# PeterParker.net
KiCad netlist of a schematic drawn in Altium Designer
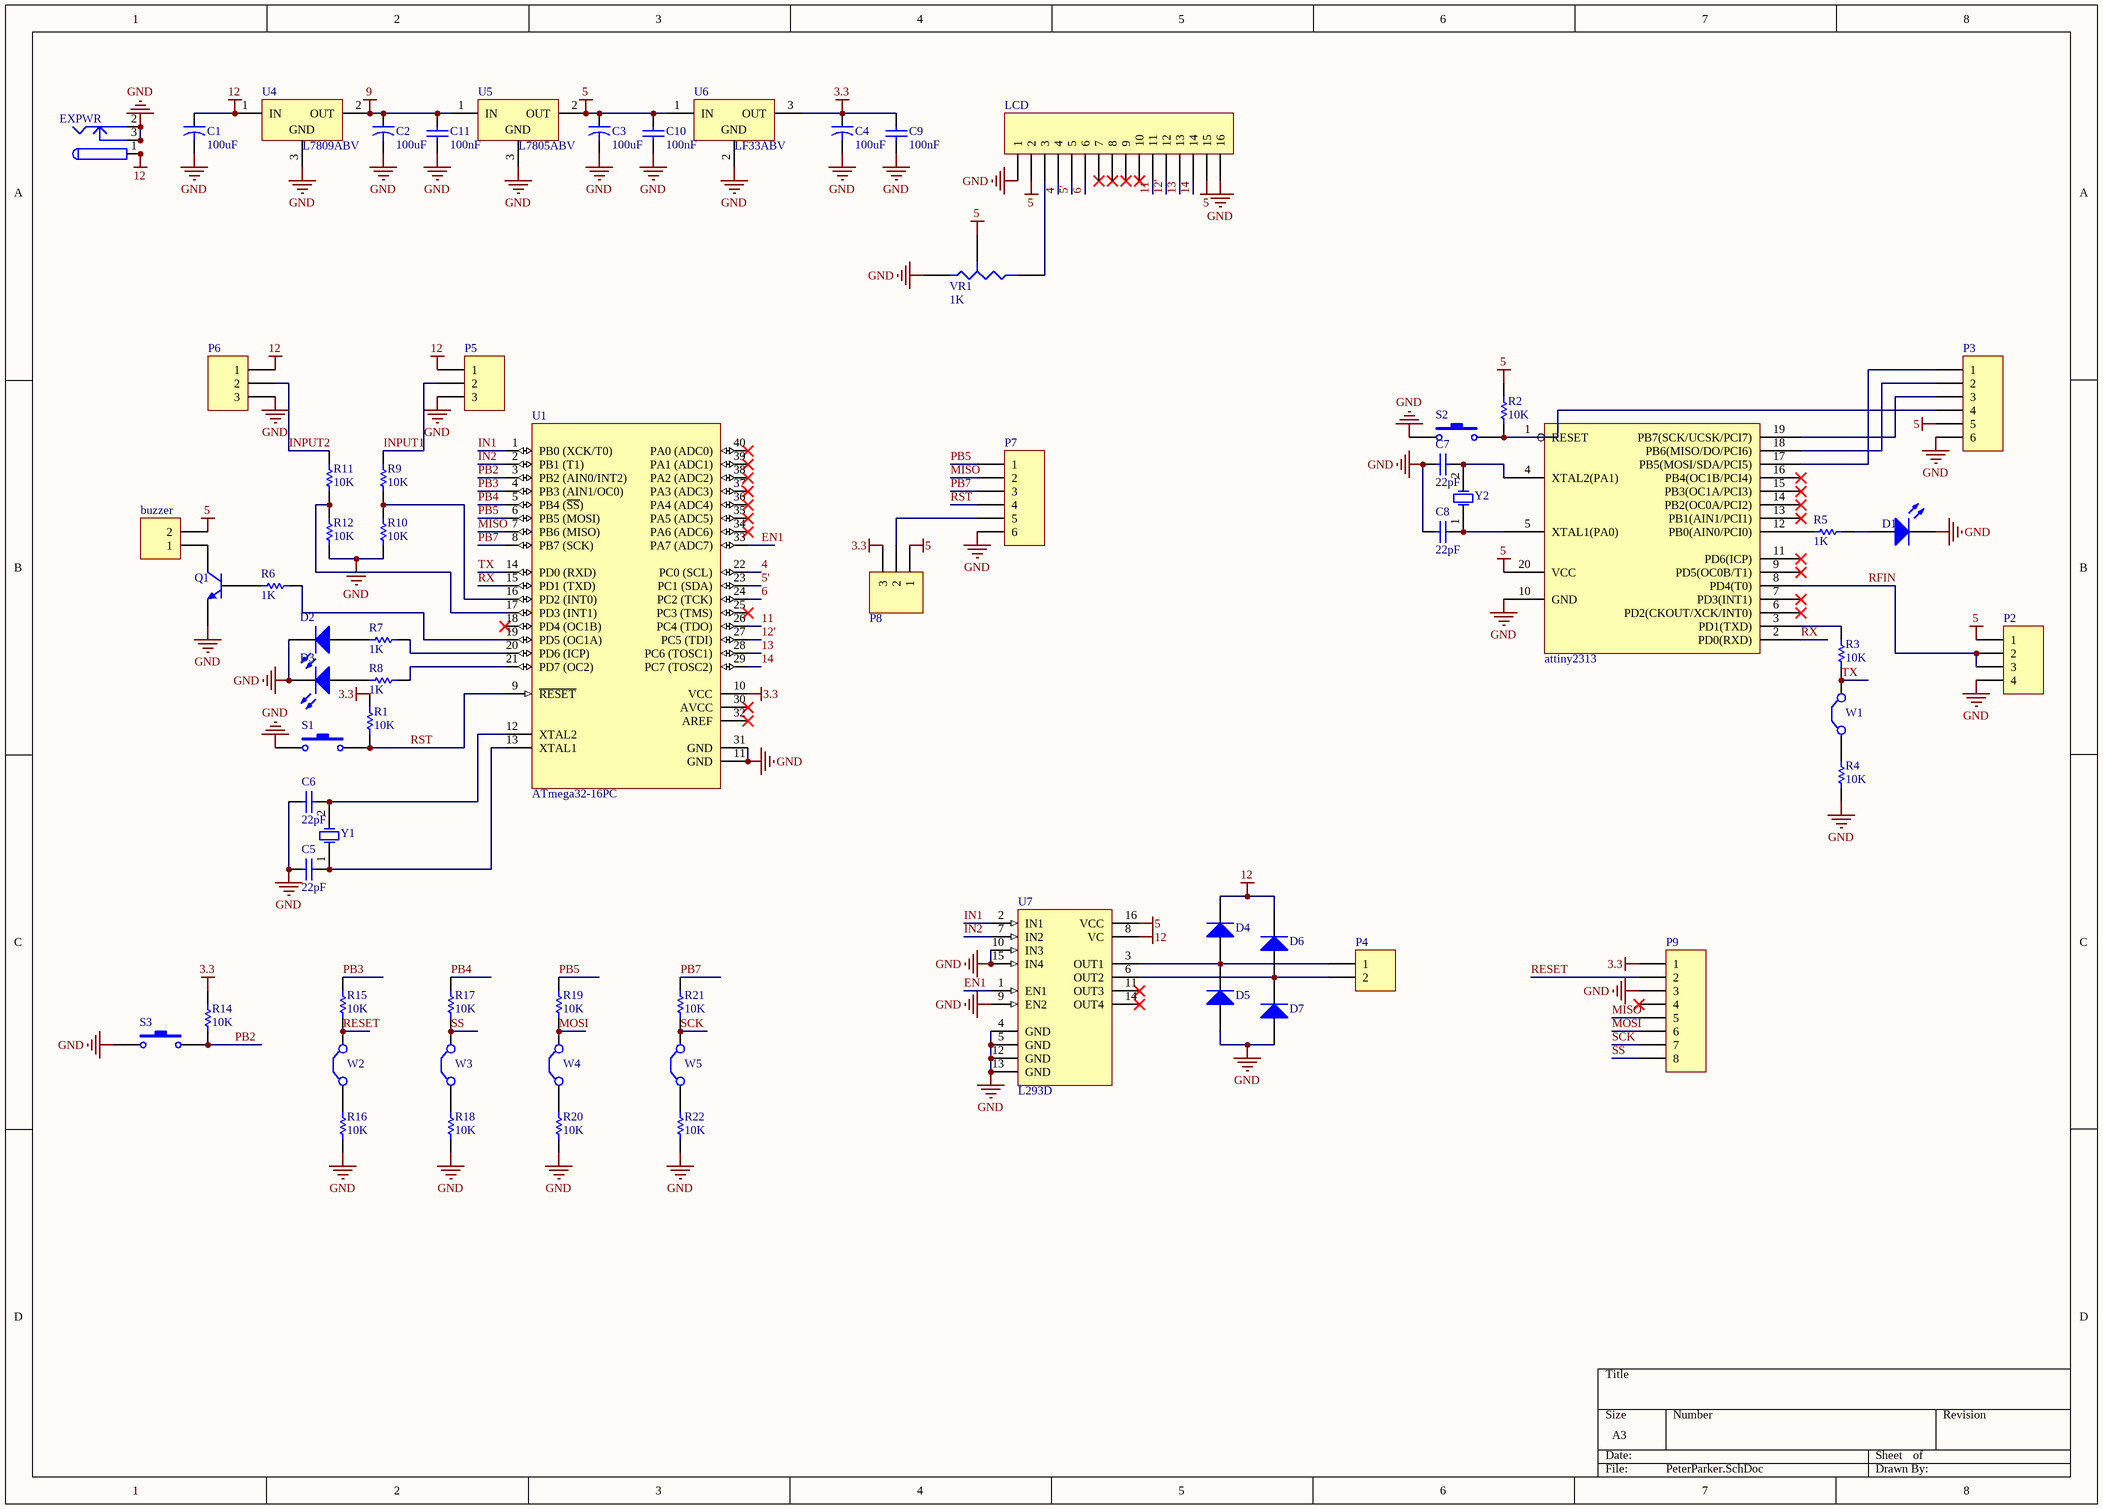
[diagram p0: PeterParker.SchDoc]

(export (version "E")
  (design (tool "Eeschema 10.0.6"))
  (components
    (comp (ref "attiny2313")
      (value "attiny2313")
      (footprint "DIP20")
      (libsource (lib "attiny2313") (part "attiny2313"))
    )
    (comp (ref "buzzer")
      (value "Header 2")
      (footprint "buzzer")
      (description "Header, 2-Pin")
      (fields (field (name "PUBLISHER") "Altium Limited"))
      (libsource (lib "Miscellaneous Connectors") (part "Header 2"))
    )
    (comp (ref "C1")
      (value "100uF")
      (footprint "CAPR5-4X5")
      (description "Capacitor")
      (fields (field (name "Comment") "Cap2") (field (name "PUBLISHER") "Altium Limited"))
      (libsource (lib "Miscellaneous Devices") (part "Cap2"))
    )
    (comp (ref "C2")
      (value "100uF")
      (footprint "CAPR5-4X5")
      (description "Capacitor")
      (fields (field (name "Comment") "Cap2") (field (name "PUBLISHER") "Altium Limited"))
      (libsource (lib "Miscellaneous Devices") (part "Cap2"))
    )
    (comp (ref "C3")
      (value "100uF")
      (footprint "CAPR5-4X5")
      (description "Capacitor")
      (fields (field (name "Comment") "Cap2") (field (name "PUBLISHER") "Altium Limited"))
      (libsource (lib "Miscellaneous Devices") (part "Cap2"))
    )
    (comp (ref "C4")
      (value "100uF")
      (footprint "CAPR5-4X5")
      (description "Capacitor")
      (fields (field (name "Comment") "Cap2") (field (name "PUBLISHER") "Altium Limited"))
      (libsource (lib "Miscellaneous Devices") (part "Cap2"))
    )
    (comp (ref "C5")
      (value "22pF")
      (footprint "tinycap")
      (description "Capacitor")
      (fields (field (name "Comment") "Cap") (field (name "PUBLISHER") "Altium Limited"))
      (libsource (lib "Miscellaneous Devices") (part "Cap"))
    )
    (comp (ref "C6")
      (value "22pF")
      (footprint "tinycap")
      (description "Capacitor")
      (fields (field (name "Comment") "Cap") (field (name "PUBLISHER") "Altium Limited"))
      (libsource (lib "Miscellaneous Devices") (part "Cap"))
    )
    (comp (ref "C7")
      (value "22pF")
      (footprint "tinycap")
      (description "Capacitor")
      (fields (field (name "Comment") "Cap") (field (name "PUBLISHER") "Altium Limited"))
      (libsource (lib "Miscellaneous Devices") (part "Cap"))
    )
    (comp (ref "C8")
      (value "22pF")
      (footprint "tinycap")
      (description "Capacitor")
      (fields (field (name "Comment") "Cap") (field (name "PUBLISHER") "Altium Limited"))
      (libsource (lib "Miscellaneous Devices") (part "Cap"))
    )
    (comp (ref "C9")
      (value "100nF")
      (footprint "RAD-0.2")
      (description "Capacitor")
      (fields (field (name "Comment") "Cap") (field (name "PUBLISHER") "Altium Limited"))
      (libsource (lib "Miscellaneous Devices") (part "Cap"))
    )
    (comp (ref "C10")
      (value "100nF")
      (footprint "RAD-0.2")
      (description "Capacitor")
      (fields (field (name "Comment") "Cap") (field (name "PUBLISHER") "Altium Limited"))
      (libsource (lib "Miscellaneous Devices") (part "Cap"))
    )
    (comp (ref "C11")
      (value "100nF")
      (footprint "RAD-0.2")
      (description "Capacitor")
      (fields (field (name "Comment") "Cap") (field (name "PUBLISHER") "Altium Limited"))
      (libsource (lib "Miscellaneous Devices") (part "Cap"))
    )
    (comp (ref "D1")
      (value "LED0")
      (footprint "LED3MM")
      (description "Typical INFRARED GaAs LED")
      (fields (field (name "PUBLISHER") "Altium Limited"))
      (libsource (lib "Miscellaneous Devices") (part "LED0"))
    )
    (comp (ref "D2")
      (value "LED0")
      (footprint "LED3MM")
      (description "Typical INFRARED GaAs LED")
      (fields (field (name "PUBLISHER") "Altium Limited"))
      (libsource (lib "Miscellaneous Devices") (part "LED0"))
    )
    (comp (ref "D3")
      (value "LED0")
      (footprint "LED3MM")
      (description "Typical INFRARED GaAs LED")
      (fields (field (name "PUBLISHER") "Altium Limited"))
      (libsource (lib "Miscellaneous Devices") (part "LED0"))
    )
    (comp (ref "D4")
      (value "Diode 1N4148")
      (footprint "Miscellaneous Devices:AXIAL-0.3")
      (description "High Conductance Fast Diode")
      (fields (field (name "PUBLISHER") "Altium Limited"))
      (libsource (lib "Miscellaneous Devices") (part "Diode 1N4148"))
    )
    (comp (ref "D5")
      (value "Diode 1N4148")
      (footprint "Miscellaneous Devices:AXIAL-0.3")
      (description "High Conductance Fast Diode")
      (fields (field (name "PUBLISHER") "Altium Limited"))
      (libsource (lib "Miscellaneous Devices") (part "Diode 1N4148"))
    )
    (comp (ref "D6")
      (value "Diode 1N4148")
      (footprint "Miscellaneous Devices:AXIAL-0.3")
      (description "High Conductance Fast Diode")
      (fields (field (name "PUBLISHER") "Altium Limited"))
      (libsource (lib "Miscellaneous Devices") (part "Diode 1N4148"))
    )
    (comp (ref "D7")
      (value "Diode 1N4148")
      (footprint "Miscellaneous Devices:AXIAL-0.3")
      (description "High Conductance Fast Diode")
      (fields (field (name "PUBLISHER") "Altium Limited"))
      (libsource (lib "Miscellaneous Devices") (part "Diode 1N4148"))
    )
    (comp (ref "EXPWR")
      (value "PWR2.5")
      (footprint "JACK1")
      (description "Low Voltage Power Supply Connector")
      (fields (field (name "PUBLISHER") "Altium Limited"))
      (libsource (lib "Miscellaneous Connectors") (part "PWR2.5"))
    )
    (comp (ref "LCD")
      (value "Header 16")
      (footprint "H1X16F")
      (description "Header, 16-Pin")
      (fields (field (name "PUBLISHER") "Altium Limited"))
      (libsource (lib "Miscellaneous Connectors") (part "Header 16"))
    )
    (comp (ref "P2")
      (value "Header 4")
      (footprint "H1X04F")
      (description "Header, 4-Pin")
      (fields (field (name "PUBLISHER") "Altium Limited"))
      (libsource (lib "Miscellaneous Connectors") (part "Header 4"))
    )
    (comp (ref "P3")
      (value "Header 6")
      (footprint "H1X06F")
      (description "Header, 6-Pin")
      (fields (field (name "PUBLISHER") "Altium Limited"))
      (libsource (lib "Miscellaneous Connectors") (part "Header 6"))
    )
    (comp (ref "P4")
      (value "Header 2")
      (footprint "H1X02F")
      (description "Header, 2-Pin")
      (fields (field (name "PUBLISHER") "Altium Limited"))
      (libsource (lib "") (part "Header 2_1"))
    )
    (comp (ref "P5")
      (value "Header 3")
      (footprint "H1X03F")
      (description "Header, 3-Pin")
      (fields (field (name "PUBLISHER") "Altium Limited"))
      (libsource (lib "") (part "Header 3_1"))
    )
    (comp (ref "P6")
      (value "Header 3")
      (footprint "H1X03F")
      (description "Header, 3-Pin")
      (fields (field (name "PUBLISHER") "Altium Limited"))
      (libsource (lib "Miscellaneous Connectors") (part "Header 3"))
    )
    (comp (ref "P7")
      (value "Header 6")
      (footprint "H1X06F")
      (description "Header, 6-Pin")
      (fields (field (name "PUBLISHER") "Altium Limited"))
      (libsource (lib "Miscellaneous Connectors") (part "Header 6"))
    )
    (comp (ref "P8")
      (value "Header 3")
      (footprint "H1X03F")
      (description "Header, 3-Pin")
      (fields (field (name "PUBLISHER") "Altium Limited"))
      (libsource (lib "Miscellaneous Connectors") (part "Header 3"))
    )
    (comp (ref "P9")
      (value "Header 8")
      (footprint "H1X08F")
      (description "Header, 8-Pin")
      (fields (field (name "PUBLISHER") "Altium Limited"))
      (libsource (lib "Miscellaneous Connectors") (part "Header 8"))
    )
    (comp (ref "Q1")
      (value "BC547")
      (footprint "SOT54")
      (description "NPN General-purpose Transistor")
      (fields (field (name "PUBLISHER") "Altium Limited"))
      (libsource (lib "Philips Discrete BJT - Low Power") (part "BC547"))
    )
    (comp (ref "R1")
      (value "10K")
      (footprint "AXIAL-0.3")
      (description "Resistor")
      (fields (field (name "Comment") "Res1") (field (name "PUBLISHER") "Altium Limited"))
      (libsource (lib "Miscellaneous Devices") (part "Res1"))
    )
    (comp (ref "R2")
      (value "10K")
      (footprint "AXIAL-0.3")
      (description "Resistor")
      (fields (field (name "Comment") "Res1") (field (name "PUBLISHER") "Altium Limited"))
      (libsource (lib "Miscellaneous Devices") (part "Res1"))
    )
    (comp (ref "R3")
      (value "10K")
      (footprint "AXIAL-0.3")
      (description "Resistor")
      (fields (field (name "Comment") "Res1") (field (name "PUBLISHER") "Altium Limited"))
      (libsource (lib "Miscellaneous Devices") (part "Res1"))
    )
    (comp (ref "R4")
      (value "10K")
      (footprint "AXIAL-0.3")
      (description "Resistor")
      (fields (field (name "Comment") "Res1") (field (name "PUBLISHER") "Altium Limited"))
      (libsource (lib "Miscellaneous Devices") (part "Res1"))
    )
    (comp (ref "R5")
      (value "1K")
      (footprint "AXIAL-0.3")
      (description "Resistor")
      (fields (field (name "Comment") "Res1") (field (name "PUBLISHER") "Altium Limited"))
      (libsource (lib "Miscellaneous Devices") (part "Res1"))
    )
    (comp (ref "R6")
      (value "1K")
      (footprint "AXIAL-0.3")
      (description "Resistor")
      (fields (field (name "Comment") "Res1") (field (name "PUBLISHER") "Altium Limited"))
      (libsource (lib "Miscellaneous Devices") (part "Res1"))
    )
    (comp (ref "R7")
      (value "1K")
      (footprint "AXIAL-0.3")
      (description "Resistor")
      (fields (field (name "Comment") "Res1") (field (name "PUBLISHER") "Altium Limited"))
      (libsource (lib "Miscellaneous Devices") (part "Res1"))
    )
    (comp (ref "R8")
      (value "1K")
      (footprint "AXIAL-0.3")
      (description "Resistor")
      (fields (field (name "Comment") "Res1") (field (name "PUBLISHER") "Altium Limited"))
      (libsource (lib "Miscellaneous Devices") (part "Res1"))
    )
    (comp (ref "R9")
      (value "10K")
      (footprint "AXIAL-0.3")
      (description "Resistor")
      (fields (field (name "Comment") "Res1") (field (name "PUBLISHER") "Altium Limited"))
      (libsource (lib "Miscellaneous Devices") (part "Res1"))
    )
    (comp (ref "R10")
      (value "10K")
      (footprint "AXIAL-0.3")
      (description "Resistor")
      (fields (field (name "Comment") "Res1") (field (name "PUBLISHER") "Altium Limited"))
      (libsource (lib "Miscellaneous Devices") (part "Res1"))
    )
    (comp (ref "R11")
      (value "10K")
      (footprint "AXIAL-0.3")
      (description "Resistor")
      (fields (field (name "Comment") "Res1") (field (name "PUBLISHER") "Altium Limited"))
      (libsource (lib "Miscellaneous Devices") (part "Res1"))
    )
    (comp (ref "R12")
      (value "10K")
      (footprint "AXIAL-0.3")
      (description "Resistor")
      (fields (field (name "Comment") "Res1") (field (name "PUBLISHER") "Altium Limited"))
      (libsource (lib "Miscellaneous Devices") (part "Res1"))
    )
    (comp (ref "R14")
      (value "10K")
      (footprint "AXIAL-0.3")
      (description "Resistor")
      (fields (field (name "Comment") "Res1") (field (name "PUBLISHER") "Altium Limited"))
      (libsource (lib "Miscellaneous Devices") (part "Res1"))
    )
    (comp (ref "R15")
      (value "10K")
      (footprint "AXIAL-0.3")
      (description "Resistor")
      (fields (field (name "Comment") "Res1") (field (name "PUBLISHER") "Altium Limited"))
      (libsource (lib "Miscellaneous Devices") (part "Res1"))
    )
    (comp (ref "R16")
      (value "10K")
      (footprint "AXIAL-0.3")
      (description "Resistor")
      (fields (field (name "Comment") "Res1") (field (name "PUBLISHER") "Altium Limited"))
      (libsource (lib "Miscellaneous Devices") (part "Res1"))
    )
    (comp (ref "R17")
      (value "10K")
      (footprint "AXIAL-0.3")
      (description "Resistor")
      (fields (field (name "Comment") "Res1") (field (name "PUBLISHER") "Altium Limited"))
      (libsource (lib "Miscellaneous Devices") (part "Res1"))
    )
    (comp (ref "R18")
      (value "10K")
      (footprint "AXIAL-0.3")
      (description "Resistor")
      (fields (field (name "Comment") "Res1") (field (name "PUBLISHER") "Altium Limited"))
      (libsource (lib "Miscellaneous Devices") (part "Res1"))
    )
    (comp (ref "R19")
      (value "10K")
      (footprint "AXIAL-0.3")
      (description "Resistor")
      (fields (field (name "Comment") "Res1") (field (name "PUBLISHER") "Altium Limited"))
      (libsource (lib "Miscellaneous Devices") (part "Res1"))
    )
    (comp (ref "R20")
      (value "10K")
      (footprint "AXIAL-0.3")
      (description "Resistor")
      (fields (field (name "Comment") "Res1") (field (name "PUBLISHER") "Altium Limited"))
      (libsource (lib "Miscellaneous Devices") (part "Res1"))
    )
    (comp (ref "R21")
      (value "10K")
      (footprint "AXIAL-0.3")
      (description "Resistor")
      (fields (field (name "Comment") "Res1") (field (name "PUBLISHER") "Altium Limited"))
      (libsource (lib "Miscellaneous Devices") (part "Res1"))
    )
    (comp (ref "R22")
      (value "10K")
      (footprint "AXIAL-0.3")
      (description "Resistor")
      (fields (field (name "Comment") "Res1") (field (name "PUBLISHER") "Altium Limited"))
      (libsource (lib "Miscellaneous Devices") (part "Res1"))
    )
    (comp (ref "S1")
      (value "SW-PB")
      (footprint "PB4")
      (description "Switch")
      (fields (field (name "PUBLISHER") "Altium Limited"))
      (libsource (lib "Miscellaneous Devices") (part "SW-PB"))
    )
    (comp (ref "S2")
      (value "SW-PB")
      (footprint "PB4")
      (description "Switch")
      (fields (field (name "PUBLISHER") "Altium Limited"))
      (libsource (lib "Miscellaneous Devices") (part "SW-PB"))
    )
    (comp (ref "S3")
      (value "SW-PB")
      (footprint "PB4")
      (description "Switch")
      (fields (field (name "PUBLISHER") "Altium Limited"))
      (libsource (lib "Miscellaneous Devices") (part "SW-PB"))
    )
    (comp (ref "U1")
      (value "ATmega32-16PC")
      (footprint "40P6")
      (description "8-Bit AVR Microcontroller with 32K Bytes of In-System Programmable Flash Memory")
      (fields (field (name "PUBLISHER") "Altium Limited"))
      (libsource (lib "Atmel Microcontroller 8-Bit AVR") (part "ATmega32-16PC"))
    )
    (comp (ref "U4")
      (value "L7809ABV")
      (footprint "TO220ABN")
      (description "Precision 1A Regulator")
      (fields (field (name "PUBLISHER") "Altium Limited"))
      (libsource (lib "ST Power Mgt Voltage Regulator") (part "L7809ABV"))
    )
    (comp (ref "U5")
      (value "L7805ABV")
      (footprint "TO220ABN")
      (description "Precision 1A Regulator")
      (fields (field (name "PUBLISHER") "Altium Limited"))
      (libsource (lib "ST Power Mgt Voltage Regulator") (part "L7805ABV"))
    )
    (comp (ref "U6")
      (value "LF33ABV")
      (footprint "TO-220A")
      (description "500mA, Very Low Drop (0.45V) Voltage Regulator")
      (fields (field (name "PUBLISHER") "Altium Limited"))
      (libsource (lib "ST Power Mgt Voltage Regulator") (part "LF33ABV"))
    )
    (comp (ref "U7")
      (value "L293D")
      (footprint "DIP16")
      (description "Push-Pull Four Channel Driver With Diode")
      (fields (field (name "PUBLISHER") "Altium Limited"))
      (libsource (lib "ST Interface DC & Stepper Motor Controller") (part "L293D"))
    )
    (comp (ref "VR1")
      (value "1K")
      (footprint "H1X03F")
      (description "Tapped Resistor")
      (fields (field (name "Comment") "Res Tap") (field (name "PUBLISHER") "Altium Limited"))
      (libsource (lib "Miscellaneous Devices") (part "Res Tap"))
    )
    (comp (ref "W1")
      (value "Jumper")
      (footprint "H1X02F")
      (description "Jumper Wire")
      (fields (field (name "PUBLISHER") "Altium Limited"))
      (libsource (lib "Miscellaneous Devices") (part "Jumper"))
    )
    (comp (ref "W2")
      (value "Jumper")
      (footprint "H1X02F")
      (description "Jumper Wire")
      (fields (field (name "PUBLISHER") "Altium Limited"))
      (libsource (lib "Miscellaneous Devices") (part "Jumper"))
    )
    (comp (ref "W3")
      (value "Jumper")
      (footprint "H1X02F")
      (description "Jumper Wire")
      (fields (field (name "PUBLISHER") "Altium Limited"))
      (libsource (lib "Miscellaneous Devices") (part "Jumper"))
    )
    (comp (ref "W4")
      (value "Jumper")
      (footprint "H1X02F")
      (description "Jumper Wire")
      (fields (field (name "PUBLISHER") "Altium Limited"))
      (libsource (lib "Miscellaneous Devices") (part "Jumper"))
    )
    (comp (ref "W5")
      (value "Jumper")
      (footprint "H1X02F")
      (description "Jumper Wire")
      (fields (field (name "PUBLISHER") "Altium Limited"))
      (libsource (lib "Miscellaneous Devices") (part "Jumper"))
    )
    (comp (ref "Y1")
      (value "XTAL")
      (footprint "CRYSTALL")
      (description "Crystal Oscillator")
      (fields (field (name "PUBLISHER") "Altium Limited"))
      (libsource (lib "Miscellaneous Devices") (part "XTAL"))
    )
    (comp (ref "Y2")
      (value "XTAL")
      (footprint "CRYSTALL")
      (description "Crystal Oscillator")
      (fields (field (name "PUBLISHER") "Altium Limited"))
      (libsource (lib "Miscellaneous Devices") (part "XTAL"))
    )
  )
  (nets
    (net (code "1") (name "/4") (class "Default")
      (node (ref "LCD") (pin "4") (pinfunction "4_4") (pintype "passive"))
      (node (ref "U1") (pin "22") (pinfunction "PC0_(SCL)_22") (pintype "bidirectional"))
    )
    (net (code "2") (name "/5'") (class "Default")
      (node (ref "LCD") (pin "5") (pinfunction "5_5") (pintype "passive"))
      (node (ref "U1") (pin "23") (pinfunction "PC1_(SDA)_23") (pintype "bidirectional"))
    )
    (net (code "3") (name "/6") (class "Default")
      (node (ref "LCD") (pin "6") (pinfunction "6_6") (pintype "passive"))
      (node (ref "U1") (pin "24") (pinfunction "PC2_(TCK)_24") (pintype "bidirectional"))
    )
    (net (code "4") (name "/11") (class "Default")
      (node (ref "LCD") (pin "11") (pinfunction "11_11") (pintype "passive"))
      (node (ref "U1") (pin "26") (pinfunction "PC4_(TDO)_26") (pintype "bidirectional"))
    )
    (net (code "5") (name "/12'") (class "Default")
      (node (ref "LCD") (pin "12") (pinfunction "12_12") (pintype "passive"))
      (node (ref "U1") (pin "27") (pinfunction "PC5_(TDI)_27") (pintype "bidirectional"))
    )
    (net (code "6") (name "/13") (class "Default")
      (node (ref "LCD") (pin "13") (pinfunction "13_13") (pintype "passive"))
      (node (ref "U1") (pin "28") (pinfunction "PC6_(TOSC1)_28") (pintype "bidirectional"))
    )
    (net (code "7") (name "/14") (class "Default")
      (node (ref "LCD") (pin "14") (pinfunction "14_14") (pintype "passive"))
      (node (ref "U1") (pin "29") (pinfunction "PC7_(TOSC2)_29") (pintype "bidirectional"))
    )
    (net (code "8") (name "/EN1") (class "Default")
      (node (ref "U1") (pin "33") (pinfunction "PA7_(ADC7)_33") (pintype "bidirectional"))
      (node (ref "U7") (pin "1") (pinfunction "EN1_1") (pintype "input"))
    )
    (net (code "9") (name "/IN1") (class "Default")
      (node (ref "U1") (pin "1") (pinfunction "PB0_(XCK/T0)_1") (pintype "bidirectional"))
      (node (ref "U7") (pin "2") (pinfunction "IN1_2") (pintype "input"))
    )
    (net (code "10") (name "/IN2") (class "Default")
      (node (ref "U1") (pin "2") (pinfunction "PB1_(T1)_2") (pintype "bidirectional"))
      (node (ref "U7") (pin "7") (pinfunction "IN2_7") (pintype "input"))
    )
    (net (code "11") (name "/INPUT1") (class "Default")
      (node (ref "P5") (pin "2") (pinfunction "2_2") (pintype "passive"))
      (node (ref "R9") (pin "1") (pinfunction "1_1") (pintype "passive"))
    )
    (net (code "12") (name "/INPUT2") (class "Default")
      (node (ref "P6") (pin "2") (pinfunction "2_2") (pintype "passive"))
      (node (ref "R11") (pin "1") (pinfunction "1_1") (pintype "passive"))
    )
    (net (code "13") (name "/MISO") (class "Default")
      (node (ref "P7") (pin "2") (pinfunction "2_2") (pintype "passive"))
      (node (ref "P9") (pin "5") (pinfunction "5_5") (pintype "passive"))
      (node (ref "U1") (pin "7") (pinfunction "PB6_(MISO)_7") (pintype "bidirectional"))
    )
    (net (code "14") (name "/MOSI") (class "Default")
      (node (ref "P9") (pin "6") (pinfunction "6_6") (pintype "passive"))
      (node (ref "R19") (pin "2") (pinfunction "2_2") (pintype "passive"))
      (node (ref "W4") (pin "2") (pinfunction "C2_2") (pintype "passive"))
    )
    (net (code "15") (name "/PB2") (class "Default")
      (node (ref "R14") (pin "1") (pinfunction "1_1") (pintype "passive"))
      (node (ref "S3") (pin "2") (pinfunction "2_2") (pintype "passive"))
      (node (ref "U1") (pin "3") (pinfunction "PB2_(AIN0/INT2)_3") (pintype "bidirectional"))
    )
    (net (code "16") (name "/PB3") (class "Default")
      (node (ref "R15") (pin "1") (pinfunction "1_1") (pintype "passive"))
      (node (ref "U1") (pin "4") (pinfunction "PB3_(AIN1/OC0)_4") (pintype "bidirectional"))
    )
    (net (code "17") (name "/PB4") (class "Default")
      (node (ref "R17") (pin "1") (pinfunction "1_1") (pintype "passive"))
      (node (ref "U1") (pin "5") (pinfunction "PB4_(~{SS})_5") (pintype "bidirectional"))
    )
    (net (code "18") (name "/PB5") (class "Default")
      (node (ref "P7") (pin "1") (pinfunction "1_1") (pintype "passive"))
      (node (ref "R19") (pin "1") (pinfunction "1_1") (pintype "passive"))
      (node (ref "U1") (pin "6") (pinfunction "PB5_(MOSI)_6") (pintype "bidirectional"))
    )
    (net (code "19") (name "/PB7") (class "Default")
      (node (ref "P7") (pin "3") (pinfunction "3_3") (pintype "passive"))
      (node (ref "R21") (pin "1") (pinfunction "1_1") (pintype "passive"))
      (node (ref "U1") (pin "8") (pinfunction "PB7_(SCK)_8") (pintype "bidirectional"))
    )
    (net (code "20") (name "/RESET") (class "Default")
      (node (ref "P9") (pin "2") (pinfunction "2_2") (pintype "passive"))
      (node (ref "R15") (pin "2") (pinfunction "2_2") (pintype "passive"))
      (node (ref "W2") (pin "2") (pinfunction "C2_2") (pintype "passive"))
    )
    (net (code "21") (name "/RFIN") (class "Default")
      (node (ref "P2") (pin "2") (pinfunction "2_2") (pintype "passive"))
      (node (ref "P2") (pin "3") (pinfunction "3_3") (pintype "passive"))
      (node (ref "attiny2313") (pin "8") (pinfunction "PD4(T0)_8") (pintype "passive"))
    )
    (net (code "22") (name "/RST") (class "Default")
      (node (ref "P7") (pin "4") (pinfunction "4_4") (pintype "passive"))
      (node (ref "R1") (pin "1") (pinfunction "1_1") (pintype "passive"))
      (node (ref "S1") (pin "2") (pinfunction "2_2") (pintype "passive"))
      (node (ref "U1") (pin "9") (pinfunction "~{RESET}_9") (pintype "input"))
    )
    (net (code "23") (name "/RX") (class "Default")
      (node (ref "U1") (pin "15") (pinfunction "PD1_(TXD)_15") (pintype "bidirectional"))
      (node (ref "attiny2313") (pin "2") (pinfunction "PD0(RXD)_2") (pintype "passive"))
    )
    (net (code "24") (name "/SCK") (class "Default")
      (node (ref "P9") (pin "7") (pinfunction "7_7") (pintype "passive"))
      (node (ref "R21") (pin "2") (pinfunction "2_2") (pintype "passive"))
      (node (ref "W5") (pin "2") (pinfunction "C2_2") (pintype "passive"))
    )
    (net (code "25") (name "/SS") (class "Default")
      (node (ref "P9") (pin "8") (pinfunction "8_8") (pintype "passive"))
      (node (ref "R17") (pin "2") (pinfunction "2_2") (pintype "passive"))
      (node (ref "W3") (pin "2") (pinfunction "C2_2") (pintype "passive"))
    )
    (net (code "26") (name "/TX") (class "Default")
      (node (ref "R3") (pin "2") (pinfunction "2_2") (pintype "passive"))
      (node (ref "U1") (pin "14") (pinfunction "PD0_(RXD)_14") (pintype "bidirectional"))
      (node (ref "W1") (pin "2") (pinfunction "C2_2") (pintype "passive"))
    )
    (net (code "27") (name "3.3") (class "Default")
      (node (ref "C4") (pin "1") (pinfunction "1_1") (pintype "passive"))
      (node (ref "C9") (pin "1") (pinfunction "1_1") (pintype "passive"))
      (node (ref "P8") (pin "3") (pinfunction "3_3") (pintype "passive"))
      (node (ref "P9") (pin "1") (pinfunction "1_1") (pintype "passive"))
      (node (ref "R1") (pin "2") (pinfunction "2_2") (pintype "passive"))
      (node (ref "R14") (pin "2") (pinfunction "2_2") (pintype "passive"))
      (node (ref "U1") (pin "10") (pinfunction "VCC_10") (pintype "power_in"))
      (node (ref "U6") (pin "3") (pinfunction "OUT_3") (pintype "power_in"))
    )
    (net (code "28") (name "5") (class "Default")
      (node (ref "C10") (pin "1") (pinfunction "1_1") (pintype "passive"))
      (node (ref "C3") (pin "1") (pinfunction "1_1") (pintype "passive"))
      (node (ref "LCD") (pin "15") (pinfunction "15_15") (pintype "passive"))
      (node (ref "LCD") (pin "2") (pinfunction "2_2") (pintype "passive"))
      (node (ref "P2") (pin "1") (pinfunction "1_1") (pintype "passive"))
      (node (ref "P3") (pin "5") (pinfunction "5_5") (pintype "passive"))
      (node (ref "P8") (pin "1") (pinfunction "1_1") (pintype "passive"))
      (node (ref "R2") (pin "2") (pinfunction "2_2") (pintype "passive"))
      (node (ref "U5") (pin "2") (pinfunction "OUT_2") (pintype "power_in"))
      (node (ref "U6") (pin "1") (pinfunction "IN_1") (pintype "power_in"))
      (node (ref "U7") (pin "16") (pinfunction "VCC_16") (pintype "power_in"))
      (node (ref "VR1") (pin "3") (pinfunction "TAP_3") (pintype "passive"))
      (node (ref "attiny2313") (pin "20") (pinfunction "VCC_20") (pintype "passive"))
      (node (ref "buzzer") (pin "2") (pinfunction "2_2") (pintype "passive"))
    )
    (net (code "29") (name "9") (class "Default")
      (node (ref "C11") (pin "1") (pinfunction "1_1") (pintype "passive"))
      (node (ref "C2") (pin "1") (pinfunction "1_1") (pintype "passive"))
      (node (ref "U4") (pin "2") (pinfunction "OUT_2") (pintype "power_in"))
      (node (ref "U5") (pin "1") (pinfunction "IN_1") (pintype "power_in"))
    )
    (net (code "30") (name "12") (class "Default")
      (node (ref "C1") (pin "1") (pinfunction "1_1") (pintype "passive"))
      (node (ref "D4") (pin "2") (pinfunction "K_2") (pintype "passive"))
      (node (ref "D6") (pin "2") (pinfunction "K_2") (pintype "passive"))
      (node (ref "EXPWR") (pin "1") (pinfunction "1_1") (pintype "power_in"))
      (node (ref "EXPWR") (pin "1A") (pinfunction "1A_1A") (pintype "power_in"))
      (node (ref "EXPWR") (pin "1B") (pinfunction "1B_1B") (pintype "power_in"))
      (node (ref "P5") (pin "1") (pinfunction "1_1") (pintype "passive"))
      (node (ref "P6") (pin "1") (pinfunction "1_1") (pintype "passive"))
      (node (ref "U4") (pin "1") (pinfunction "IN_1") (pintype "power_in"))
      (node (ref "U7") (pin "8") (pinfunction "VC_8") (pintype "power_in"))
    )
    (net (code "31") (name "GND") (class "Default")
      (node (ref "C1") (pin "2") (pinfunction "2_2") (pintype "passive"))
      (node (ref "C10") (pin "2") (pinfunction "2_2") (pintype "passive"))
      (node (ref "C11") (pin "2") (pinfunction "2_2") (pintype "passive"))
      (node (ref "C2") (pin "2") (pinfunction "2_2") (pintype "passive"))
      (node (ref "C3") (pin "2") (pinfunction "2_2") (pintype "passive"))
      (node (ref "C4") (pin "2") (pinfunction "2_2") (pintype "passive"))
      (node (ref "C5") (pin "1") (pinfunction "1_1") (pintype "passive"))
      (node (ref "C6") (pin "2") (pinfunction "2_2") (pintype "passive"))
      (node (ref "C7") (pin "2") (pinfunction "2_2") (pintype "passive"))
      (node (ref "C8") (pin "2") (pinfunction "2_2") (pintype "passive"))
      (node (ref "C9") (pin "2") (pinfunction "2_2") (pintype "passive"))
      (node (ref "D1") (pin "2") (pinfunction "K_2") (pintype "passive"))
      (node (ref "D2") (pin "2") (pinfunction "K_2") (pintype "passive"))
      (node (ref "D3") (pin "2") (pinfunction "K_2") (pintype "passive"))
      (node (ref "D5") (pin "1") (pinfunction "A_1") (pintype "passive"))
      (node (ref "D7") (pin "1") (pinfunction "A_1") (pintype "passive"))
      (node (ref "EXPWR") (pin "2") (pinfunction "2_2") (pintype "power_in"))
      (node (ref "EXPWR") (pin "2A") (pinfunction "2A_2A") (pintype "power_in"))
      (node (ref "EXPWR") (pin "2B") (pinfunction "2B_2B") (pintype "power_in"))
      (node (ref "EXPWR") (pin "3") (pinfunction "3_3") (pintype "power_in"))
      (node (ref "EXPWR") (pin "3A") (pinfunction "3A_3A") (pintype "power_in"))
      (node (ref "EXPWR") (pin "3B") (pinfunction "3B_3B") (pintype "power_in"))
      (node (ref "LCD") (pin "1") (pinfunction "1_1") (pintype "passive"))
      (node (ref "LCD") (pin "16") (pinfunction "16_16") (pintype "passive"))
      (node (ref "P2") (pin "4") (pinfunction "4_4") (pintype "passive"))
      (node (ref "P3") (pin "6") (pinfunction "6_6") (pintype "passive"))
      (node (ref "P5") (pin "3") (pinfunction "3_3") (pintype "passive"))
      (node (ref "P6") (pin "3") (pinfunction "3_3") (pintype "passive"))
      (node (ref "P7") (pin "6") (pinfunction "6_6") (pintype "passive"))
      (node (ref "P9") (pin "3") (pinfunction "3_3") (pintype "passive"))
      (node (ref "Q1") (pin "1") (pinfunction "E_1") (pintype "passive"))
      (node (ref "R10") (pin "2") (pinfunction "2_2") (pintype "passive"))
      (node (ref "R12") (pin "2") (pinfunction "2_2") (pintype "passive"))
      (node (ref "R16") (pin "2") (pinfunction "2_2") (pintype "passive"))
      (node (ref "R18") (pin "2") (pinfunction "2_2") (pintype "passive"))
      (node (ref "R20") (pin "2") (pinfunction "2_2") (pintype "passive"))
      (node (ref "R22") (pin "2") (pinfunction "2_2") (pintype "passive"))
      (node (ref "R4") (pin "2") (pinfunction "2_2") (pintype "passive"))
      (node (ref "S1") (pin "1") (pinfunction "1_1") (pintype "passive"))
      (node (ref "S2") (pin "1") (pinfunction "1_1") (pintype "passive"))
      (node (ref "S3") (pin "1") (pinfunction "1_1") (pintype "passive"))
      (node (ref "U1") (pin "11") (pinfunction "GND_11") (pintype "power_in"))
      (node (ref "U1") (pin "31") (pinfunction "GND_31") (pintype "power_in"))
      (node (ref "U4") (pin "3") (pinfunction "GND_3") (pintype "power_in"))
      (node (ref "U5") (pin "3") (pinfunction "GND_3") (pintype "power_in"))
      (node (ref "U6") (pin "2") (pinfunction "GND_2") (pintype "power_in"))
      (node (ref "U7") (pin "10") (pinfunction "IN3_10") (pintype "input"))
      (node (ref "U7") (pin "12") (pinfunction "GND_12") (pintype "power_in"))
      (node (ref "U7") (pin "13") (pinfunction "GND_13") (pintype "power_in"))
      (node (ref "U7") (pin "15") (pinfunction "IN4_15") (pintype "input"))
      (node (ref "U7") (pin "4") (pinfunction "GND_4") (pintype "power_in"))
      (node (ref "U7") (pin "5") (pinfunction "GND_5") (pintype "power_in"))
      (node (ref "U7") (pin "9") (pinfunction "EN2_9") (pintype "input"))
      (node (ref "VR1") (pin "1") (pinfunction "A_1") (pintype "passive"))
      (node (ref "attiny2313") (pin "10") (pinfunction "GND_10") (pintype "passive"))
    )
    (net (code "32") (name "Net-(D1-A)") (class "Default")
      (node (ref "D1") (pin "1") (pinfunction "A_1") (pintype "passive"))
      (node (ref "R5") (pin "1") (pinfunction "1_1") (pintype "passive"))
    )
    (net (code "33") (name "Net-(D2-A)") (class "Default")
      (node (ref "D2") (pin "1") (pinfunction "A_1") (pintype "passive"))
      (node (ref "R7") (pin "2") (pinfunction "2_2") (pintype "passive"))
    )
    (net (code "34") (name "Net-(D3-A)") (class "Default")
      (node (ref "D3") (pin "1") (pinfunction "A_1") (pintype "passive"))
      (node (ref "R8") (pin "2") (pinfunction "2_2") (pintype "passive"))
    )
    (net (code "35") (name "Net-(D4-A)") (class "Default")
      (node (ref "D4") (pin "1") (pinfunction "A_1") (pintype "passive"))
      (node (ref "D5") (pin "2") (pinfunction "K_2") (pintype "passive"))
      (node (ref "P4") (pin "1") (pinfunction "1_1") (pintype "passive"))
      (node (ref "U7") (pin "3") (pinfunction "OUT1_3") (pintype "tri_state"))
    )
    (net (code "36") (name "Net-(D6-A)") (class "Default")
      (node (ref "D6") (pin "1") (pinfunction "A_1") (pintype "passive"))
      (node (ref "D7") (pin "2") (pinfunction "K_2") (pintype "passive"))
      (node (ref "P4") (pin "2") (pinfunction "2_2") (pintype "passive"))
      (node (ref "U7") (pin "6") (pinfunction "OUT2_6") (pintype "tri_state"))
    )
    (net (code "37") (name "Net-(P7-Pad5)") (class "Default")
      (node (ref "P7") (pin "5") (pinfunction "5_5") (pintype "passive"))
      (node (ref "P8") (pin "2") (pinfunction "2_2") (pintype "passive"))
    )
    (net (code "38") (name "Net-(Q1-B)") (class "Default")
      (node (ref "Q1") (pin "2") (pinfunction "B_2") (pintype "passive"))
      (node (ref "R6") (pin "2") (pinfunction "2_2") (pintype "passive"))
    )
    (net (code "39") (name "Net-(Q1-C)") (class "Default")
      (node (ref "Q1") (pin "3") (pinfunction "C_3") (pintype "passive"))
      (node (ref "buzzer") (pin "1") (pinfunction "1_1") (pintype "passive"))
    )
    (net (code "40") (name "Net-(U1-PD2_(INT0))") (class "Default")
      (node (ref "R10") (pin "1") (pinfunction "1_1") (pintype "passive"))
      (node (ref "R9") (pin "2") (pinfunction "2_2") (pintype "passive"))
      (node (ref "U1") (pin "16") (pinfunction "PD2_(INT0)_16") (pintype "bidirectional"))
    )
    (net (code "41") (name "Net-(U1-PD3_(INT1))") (class "Default")
      (node (ref "R11") (pin "2") (pinfunction "2_2") (pintype "passive"))
      (node (ref "R12") (pin "1") (pinfunction "1_1") (pintype "passive"))
      (node (ref "U1") (pin "17") (pinfunction "PD3_(INT1)_17") (pintype "bidirectional"))
    )
    (net (code "42") (name "Net-(U1-PD5_(OC1A))") (class "Default")
      (node (ref "R6") (pin "1") (pinfunction "1_1") (pintype "passive"))
      (node (ref "U1") (pin "19") (pinfunction "PD5_(OC1A)_19") (pintype "bidirectional"))
    )
    (net (code "43") (name "Net-(U1-PD6_(ICP))") (class "Default")
      (node (ref "R7") (pin "1") (pinfunction "1_1") (pintype "passive"))
      (node (ref "U1") (pin "20") (pinfunction "PD6_(ICP)_20") (pintype "bidirectional"))
    )
    (net (code "44") (name "Net-(U1-PD7_(OC2))") (class "Default")
      (node (ref "R8") (pin "1") (pinfunction "1_1") (pintype "passive"))
      (node (ref "U1") (pin "21") (pinfunction "PD7_(OC2)_21") (pintype "bidirectional"))
    )
    (net (code "45") (name "Net-(U1-XTAL1)") (class "Default")
      (node (ref "C5") (pin "2") (pinfunction "2_2") (pintype "passive"))
      (node (ref "U1") (pin "13") (pinfunction "XTAL1_13") (pintype "passive"))
      (node (ref "Y1") (pin "1") (pinfunction "OSC1_1") (pintype "passive"))
    )
    (net (code "46") (name "Net-(U1-XTAL2)") (class "Default")
      (node (ref "C6") (pin "1") (pinfunction "1_1") (pintype "passive"))
      (node (ref "U1") (pin "12") (pinfunction "XTAL2_12") (pintype "passive"))
      (node (ref "Y1") (pin "2") (pinfunction "OSC2_2") (pintype "passive"))
    )
    (net (code "47") (name "Net-(VR1-B)") (class "Default")
      (node (ref "LCD") (pin "3") (pinfunction "3_3") (pintype "passive"))
      (node (ref "VR1") (pin "2") (pinfunction "B_2") (pintype "passive"))
    )
    (net (code "48") (name "Net-(W1-C1)") (class "Default")
      (node (ref "R4") (pin "1") (pinfunction "1_1") (pintype "passive"))
      (node (ref "W1") (pin "1") (pinfunction "C1_1") (pintype "passive"))
    )
    (net (code "49") (name "Net-(W2-C1)") (class "Default")
      (node (ref "R16") (pin "1") (pinfunction "1_1") (pintype "passive"))
      (node (ref "W2") (pin "1") (pinfunction "C1_1") (pintype "passive"))
    )
    (net (code "50") (name "Net-(W3-C1)") (class "Default")
      (node (ref "R18") (pin "1") (pinfunction "1_1") (pintype "passive"))
      (node (ref "W3") (pin "1") (pinfunction "C1_1") (pintype "passive"))
    )
    (net (code "51") (name "Net-(W4-C1)") (class "Default")
      (node (ref "R20") (pin "1") (pinfunction "1_1") (pintype "passive"))
      (node (ref "W4") (pin "1") (pinfunction "C1_1") (pintype "passive"))
    )
    (net (code "52") (name "Net-(W5-C1)") (class "Default")
      (node (ref "R22") (pin "1") (pinfunction "1_1") (pintype "passive"))
      (node (ref "W5") (pin "1") (pinfunction "C1_1") (pintype "passive"))
    )
    (net (code "53") (name "Net-(Y2-OSC1)") (class "Default")
      (node (ref "C8") (pin "1") (pinfunction "1_1") (pintype "passive"))
      (node (ref "Y2") (pin "1") (pinfunction "OSC1_1") (pintype "passive"))
      (node (ref "attiny2313") (pin "5") (pinfunction "XTAL1(PA0)_5") (pintype "passive"))
    )
    (net (code "54") (name "Net-(Y2-OSC2)") (class "Default")
      (node (ref "C7") (pin "1") (pinfunction "1_1") (pintype "passive"))
      (node (ref "Y2") (pin "2") (pinfunction "OSC2_2") (pintype "passive"))
      (node (ref "attiny2313") (pin "4") (pinfunction "XTAL2(PA1)_4") (pintype "passive"))
    )
    (net (code "55") (name "Net-(attiny2313-PB0(AIN0{slash}PCI0))") (class "Default")
      (node (ref "R5") (pin "2") (pinfunction "2_2") (pintype "passive"))
      (node (ref "attiny2313") (pin "12") (pinfunction "PB0(AIN0/PCI0)_12") (pintype "passive"))
    )
    (net (code "56") (name "Net-(attiny2313-PB5(MOSI{slash}SDA{slash}PCI5))") (class "Default")
      (node (ref "P3") (pin "1") (pinfunction "1_1") (pintype "passive"))
      (node (ref "attiny2313") (pin "17") (pinfunction "PB5(MOSI/SDA/PCI5)_17") (pintype "passive"))
    )
    (net (code "57") (name "Net-(attiny2313-PB6(MISO{slash}DO{slash}PCI6))") (class "Default")
      (node (ref "P3") (pin "2") (pinfunction "2_2") (pintype "passive"))
      (node (ref "attiny2313") (pin "18") (pinfunction "PB6(MISO/DO/PCI6)_18") (pintype "passive"))
    )
    (net (code "58") (name "Net-(attiny2313-PB7(SCK{slash}UCSK{slash}PCI7))") (class "Default")
      (node (ref "P3") (pin "3") (pinfunction "3_3") (pintype "passive"))
      (node (ref "attiny2313") (pin "19") (pinfunction "PB7(SCK/UCSK/PCI7)_19") (pintype "passive"))
    )
    (net (code "59") (name "Net-(attiny2313-PD1(TXD))") (class "Default")
      (node (ref "R3") (pin "1") (pinfunction "1_1") (pintype "passive"))
      (node (ref "attiny2313") (pin "3") (pinfunction "PD1(TXD)_3") (pintype "passive"))
    )
    (net (code "60") (name "Net-(attiny2313-RESET)") (class "Default")
      (node (ref "P3") (pin "4") (pinfunction "4_4") (pintype "passive"))
      (node (ref "R2") (pin "1") (pinfunction "1_1") (pintype "passive"))
      (node (ref "S2") (pin "2") (pinfunction "2_2") (pintype "passive"))
      (node (ref "attiny2313") (pin "1") (pinfunction "RESET_1") (pintype "passive"))
    )
    (net (code "61") (name "unconnected-(LCD-Pad7)") (class "Default")
      (node (ref "LCD") (pin "7") (pinfunction "7_7") (pintype "passive+no_connect"))
    )
    (net (code "62") (name "unconnected-(LCD-Pad8)") (class "Default")
      (node (ref "LCD") (pin "8") (pinfunction "8_8") (pintype "passive+no_connect"))
    )
    (net (code "63") (name "unconnected-(LCD-Pad9)") (class "Default")
      (node (ref "LCD") (pin "9") (pinfunction "9_9") (pintype "passive+no_connect"))
    )
    (net (code "64") (name "unconnected-(LCD-Pad10)") (class "Default")
      (node (ref "LCD") (pin "10") (pinfunction "10_10") (pintype "passive+no_connect"))
    )
    (net (code "65") (name "unconnected-(P9-Pad4)") (class "Default")
      (node (ref "P9") (pin "4") (pinfunction "4_4") (pintype "passive+no_connect"))
    )
    (net (code "66") (name "unconnected-(U1-AREF-Pad32)") (class "Default")
      (node (ref "U1") (pin "32") (pinfunction "AREF_32") (pintype "passive+no_connect"))
    )
    (net (code "67") (name "unconnected-(U1-AVCC-Pad30)") (class "Default")
      (node (ref "U1") (pin "30") (pinfunction "AVCC_30") (pintype "power_in+no_connect"))
    )
    (net (code "68") (name "unconnected-(U1-PA0_(ADC0)-Pad40)") (class "Default")
      (node (ref "U1") (pin "40") (pinfunction "PA0_(ADC0)_40") (pintype "bidirectional+no_connect"))
    )
    (net (code "69") (name "unconnected-(U1-PA1_(ADC1)-Pad39)") (class "Default")
      (node (ref "U1") (pin "39") (pinfunction "PA1_(ADC1)_39") (pintype "bidirectional+no_connect"))
    )
    (net (code "70") (name "unconnected-(U1-PA2_(ADC2)-Pad38)") (class "Default")
      (node (ref "U1") (pin "38") (pinfunction "PA2_(ADC2)_38") (pintype "bidirectional+no_connect"))
    )
    (net (code "71") (name "unconnected-(U1-PA3_(ADC3)-Pad37)") (class "Default")
      (node (ref "U1") (pin "37") (pinfunction "PA3_(ADC3)_37") (pintype "bidirectional+no_connect"))
    )
    (net (code "72") (name "unconnected-(U1-PA4_(ADC4)-Pad36)") (class "Default")
      (node (ref "U1") (pin "36") (pinfunction "PA4_(ADC4)_36") (pintype "bidirectional+no_connect"))
    )
    (net (code "73") (name "unconnected-(U1-PA5_(ADC5)-Pad35)") (class "Default")
      (node (ref "U1") (pin "35") (pinfunction "PA5_(ADC5)_35") (pintype "bidirectional+no_connect"))
    )
    (net (code "74") (name "unconnected-(U1-PA6_(ADC6)-Pad34)") (class "Default")
      (node (ref "U1") (pin "34") (pinfunction "PA6_(ADC6)_34") (pintype "bidirectional+no_connect"))
    )
    (net (code "75") (name "unconnected-(U1-PC3_(TMS)-Pad25)") (class "Default")
      (node (ref "U1") (pin "25") (pinfunction "PC3_(TMS)_25") (pintype "bidirectional+no_connect"))
    )
    (net (code "76") (name "unconnected-(U1-PD4_(OC1B)-Pad18)") (class "Default")
      (node (ref "U1") (pin "18") (pinfunction "PD4_(OC1B)_18") (pintype "bidirectional+no_connect"))
    )
    (net (code "77") (name "unconnected-(U7-OUT3-Pad11)") (class "Default")
      (node (ref "U7") (pin "11") (pinfunction "OUT3_11") (pintype "tri_state+no_connect"))
    )
    (net (code "78") (name "unconnected-(U7-OUT4-Pad14)") (class "Default")
      (node (ref "U7") (pin "14") (pinfunction "OUT4_14") (pintype "tri_state+no_connect"))
    )
    (net (code "79") (name "unconnected-(attiny2313-PB1(AIN1{slash}PCI1)-Pad13)") (class "Default")
      (node (ref "attiny2313") (pin "13") (pinfunction "PB1(AIN1/PCI1)_13") (pintype "passive+no_connect"))
    )
    (net (code "80") (name "unconnected-(attiny2313-PB2(OC0A{slash}PCI2)-Pad14)") (class "Default")
      (node (ref "attiny2313") (pin "14") (pinfunction "PB2(OC0A/PCI2)_14") (pintype "passive+no_connect"))
    )
    (net (code "81") (name "unconnected-(attiny2313-PB3(OC1A{slash}PCI3)-Pad15)") (class "Default")
      (node (ref "attiny2313") (pin "15") (pinfunction "PB3(OC1A/PCI3)_15") (pintype "passive+no_connect"))
    )
    (net (code "82") (name "unconnected-(attiny2313-PB4(OC1B{slash}PCI4)-Pad16)") (class "Default")
      (node (ref "attiny2313") (pin "16") (pinfunction "PB4(OC1B/PCI4)_16") (pintype "passive+no_connect"))
    )
    (net (code "83") (name "unconnected-(attiny2313-PD2(CKOUT{slash}XCK{slash}INT0)-Pad6)") (class "Default")
      (node (ref "attiny2313") (pin "6") (pinfunction "PD2(CKOUT/XCK/INT0)_6") (pintype "passive+no_connect"))
    )
    (net (code "84") (name "unconnected-(attiny2313-PD3(INT1)-Pad7)") (class "Default")
      (node (ref "attiny2313") (pin "7") (pinfunction "PD3(INT1)_7") (pintype "passive+no_connect"))
    )
    (net (code "85") (name "unconnected-(attiny2313-PD5(OC0B{slash}T1)-Pad9)") (class "Default")
      (node (ref "attiny2313") (pin "9") (pinfunction "PD5(OC0B/T1)_9") (pintype "passive+no_connect"))
    )
    (net (code "86") (name "unconnected-(attiny2313-PD6(ICP)-Pad11)") (class "Default")
      (node (ref "attiny2313") (pin "11") (pinfunction "PD6(ICP)_11") (pintype "passive+no_connect"))
    )
  )
)
